# untitled.net
KiCad netlist of a schematic drawn in EAGLE
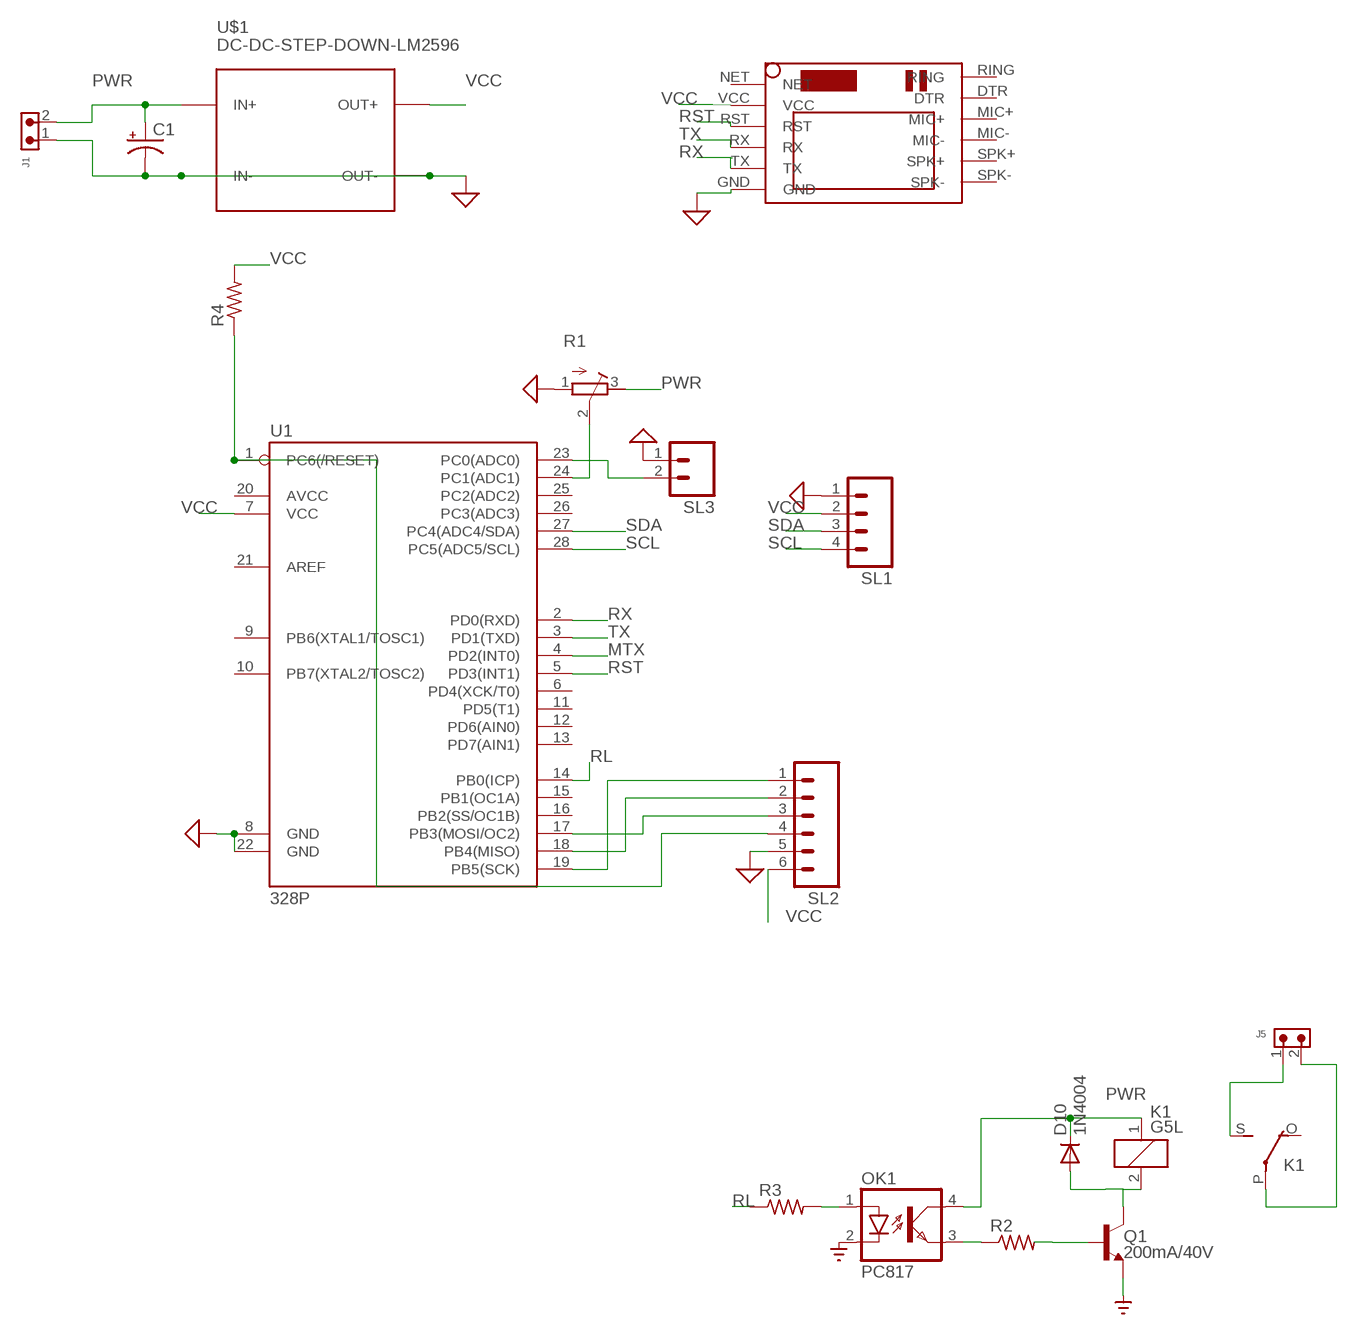
[diagram p0: schematic, sheet 1]

(export (version "E")
  (design (tool "Eeschema 10.0.6"))
  (components
    (comp (ref "C1")
      (value "CPOL-USE7.5-16")
      (footprint "eagle-import:E7,5-16")
      (libsource (lib "eagle-import") (part "CPOL-USE7.5-16"))
    )
    (comp (ref "D10")
      (value "1N4004")
      (footprint "eagle-import:DO41-10")
      (libsource (lib "eagle-import") (part "1N4004"))
    )
    (comp (ref "J1")
      (value "691305530002")
      (footprint "eagle-import:691305530002")
      (libsource (lib "eagle-import") (part "691305530002"))
    )
    (comp (ref "J5")
      (value "691305530002")
      (footprint "eagle-import:691305530002")
      (libsource (lib "eagle-import") (part "691305530002"))
    )
    (comp (ref "K1")
      (value "G5L")
      (footprint "eagle-import:G5LE")
      (libsource (lib "eagle-import") (part "G5L"))
    )
    (comp (ref "OK1")
      (value "PC817")
      (footprint "eagle-import:DIL04")
      (fields (field (name "MPN") "PC817X4J000F"))
      (libsource (lib "eagle-import") (part "PC817"))
    )
    (comp (ref "Q1")
      (value "200mA/40V")
      (footprint "eagle-import:TO-92")
      (libsource (lib "eagle-import") (part "TRANS_NPN-2N3904"))
    )
    (comp (ref "R1")
      (value "R-TRIMM3296Y")
      (footprint "eagle-import:RTRIM3296Y")
      (libsource (lib "eagle-import") (part "R-TRIMM3296Y"))
    )
    (comp (ref "R2")
      (value "R-US_0207/10")
      (footprint "eagle-import:0207_10")
      (libsource (lib "eagle-import") (part "R-US_0207/10"))
    )
    (comp (ref "R3")
      (value "R-US_0207/12")
      (footprint "eagle-import:0207_12")
      (libsource (lib "eagle-import") (part "adafruit_420_R-US_0207/12"))
    )
    (comp (ref "R4")
      (value "R-US_0207/10")
      (footprint "eagle-import:0207_10")
      (libsource (lib "eagle-import") (part "R-US_0207/10"))
    )
    (comp (ref "SL1")
      (value "M04")
      (footprint "eagle-import:04P")
      (libsource (lib "eagle-import") (part "M04"))
    )
    (comp (ref "SL2")
      (value "M06")
      (footprint "eagle-import:06P")
      (libsource (lib "eagle-import") (part "M06"))
    )
    (comp (ref "SL3")
      (value "M02")
      (footprint "eagle-import:02P")
      (libsource (lib "eagle-import") (part "M02"))
    )
    (comp (ref "U$1")
      (value "DC-DC-STEP-DOWN-LM2596")
      (footprint "eagle-import:DC-DC-STEP-DOWN-LM2596")
      (libsource (lib "eagle-import") (part "DC-DC-STEP-DOWN-LM2596"))
    )
    (comp (ref "U$2")
      (value "SIM800LMODULE")
      (footprint "eagle-import:SIM800LMODULE")
      (libsource (lib "eagle-import") (part "SIM800LMODULE"))
    )
    (comp (ref "U1")
      (value "328P")
      (footprint "eagle-import:DIP28")
      (libsource (lib "eagle-import") (part "ATMEGA328P_PDIP"))
    )
  )
  (nets
    (net (code "1") (name "/MTX") (class "Default")
      (node (ref "U1") (pin "4") (pinfunction "PD2(INT0)_4") (pintype "bidirectional"))
    )
    (net (code "2") (name "/PWR") (class "Default")
      (node (ref "C1") (pin "+") (pinfunction "+_+") (pintype "passive"))
      (node (ref "D10") (pin "C") (pinfunction "C_C") (pintype "passive"))
      (node (ref "J1") (pin "2") (pinfunction "2_2") (pintype "passive"))
      (node (ref "K1") (pin "1") (pinfunction "1_1") (pintype "passive"))
      (node (ref "OK1") (pin "4") (pinfunction "COL_4") (pintype "passive"))
      (node (ref "R1") (pin "3") (pinfunction "E_3") (pintype "passive"))
      (node (ref "U$1") (pin "IN+") (pinfunction "IN+_IN+") (pintype "bidirectional"))
    )
    (net (code "3") (name "/RL") (class "Default")
      (node (ref "R3") (pin "1") (pinfunction "1_1") (pintype "passive"))
      (node (ref "U1") (pin "14") (pinfunction "PB0(ICP)_14") (pintype "bidirectional"))
    )
    (net (code "4") (name "/RST") (class "Default")
      (node (ref "U$2") (pin "RST") (pinfunction "RST_RST") (pintype "bidirectional"))
      (node (ref "U1") (pin "5") (pinfunction "PD3(INT1)_5") (pintype "bidirectional"))
    )
    (net (code "5") (name "/RX") (class "Default")
      (node (ref "U$2") (pin "TX") (pinfunction "TX_TX") (pintype "bidirectional"))
      (node (ref "U1") (pin "2") (pinfunction "PD0(RXD)_2") (pintype "bidirectional"))
    )
    (net (code "6") (name "/SCL") (class "Default")
      (node (ref "SL1") (pin "4") (pinfunction "4_4") (pintype "passive"))
      (node (ref "U1") (pin "28") (pinfunction "PC5(ADC5/SCL)_28") (pintype "bidirectional"))
    )
    (net (code "7") (name "/SDA") (class "Default")
      (node (ref "SL1") (pin "3") (pinfunction "3_3") (pintype "passive"))
      (node (ref "U1") (pin "27") (pinfunction "PC4(ADC4/SDA)_27") (pintype "bidirectional"))
    )
    (net (code "8") (name "/TX") (class "Default")
      (node (ref "U$2") (pin "RX") (pinfunction "RX_RX") (pintype "bidirectional"))
      (node (ref "U1") (pin "3") (pinfunction "PD1(TXD)_3") (pintype "bidirectional"))
    )
    (net (code "9") (name "/VCC") (class "Default")
      (node (ref "R4") (pin "2") (pinfunction "2_2") (pintype "passive"))
      (node (ref "SL1") (pin "2") (pinfunction "2_2") (pintype "passive"))
      (node (ref "SL2") (pin "6") (pinfunction "6_6") (pintype "passive"))
      (node (ref "U$1") (pin "OUT+") (pinfunction "OUT+_OUT+") (pintype "bidirectional"))
      (node (ref "U$2") (pin "VCC") (pinfunction "VCC_VCC") (pintype "bidirectional"))
      (node (ref "U1") (pin "7") (pinfunction "VCC_7") (pintype "bidirectional"))
    )
    (net (code "10") (name "Net-(J5-Pad1)") (class "Default")
      (node (ref "J5") (pin "1") (pinfunction "1_1") (pintype "passive"))
      (node (ref "K1") (pin "S") (pinfunction "S_S") (pintype "passive"))
    )
    (net (code "11") (name "Net-(J5-Pad2)") (class "Default")
      (node (ref "J5") (pin "2") (pinfunction "2_2") (pintype "passive"))
      (node (ref "K1") (pin "P") (pinfunction "P_P") (pintype "passive"))
    )
    (net (code "12") (name "Net-(OK1-A)") (class "Default")
      (node (ref "OK1") (pin "1") (pinfunction "A_1") (pintype "passive"))
      (node (ref "R3") (pin "2") (pinfunction "2_2") (pintype "passive"))
    )
    (net (code "13") (name "Net-(OK1-EMIT)") (class "Default")
      (node (ref "OK1") (pin "3") (pinfunction "EMIT_3") (pintype "passive"))
      (node (ref "R2") (pin "1") (pinfunction "1_1") (pintype "passive"))
    )
    (net (code "14") (name "Net-(Q1-B)") (class "Default")
      (node (ref "Q1") (pin "2") (pinfunction "B_2") (pintype "passive"))
      (node (ref "R2") (pin "2") (pinfunction "2_2") (pintype "passive"))
    )
    (net (code "15") (name "Net-(Q1-C)") (class "Default")
      (node (ref "D10") (pin "A") (pinfunction "A_A") (pintype "passive"))
      (node (ref "K1") (pin "2") (pinfunction "2_2") (pintype "passive"))
      (node (ref "Q1") (pin "3") (pinfunction "C_3") (pintype "passive"))
    )
    (net (code "16") (name "Net-(R1-S)") (class "Default")
      (node (ref "R1") (pin "2") (pinfunction "S_2") (pintype "passive"))
      (node (ref "U1") (pin "24") (pinfunction "PC1(ADC1)_24") (pintype "bidirectional"))
    )
    (net (code "17") (name "Net-(U1-PB3(MOSI{slash}OC2))") (class "Default")
      (node (ref "SL2") (pin "3") (pinfunction "3_3") (pintype "passive"))
      (node (ref "U1") (pin "17") (pinfunction "PB3(MOSI/OC2)_17") (pintype "bidirectional"))
    )
    (net (code "18") (name "Net-(U1-PB4(MISO))") (class "Default")
      (node (ref "SL2") (pin "2") (pinfunction "2_2") (pintype "passive"))
      (node (ref "U1") (pin "18") (pinfunction "PB4(MISO)_18") (pintype "bidirectional"))
    )
    (net (code "19") (name "Net-(U1-PB5(SCK))") (class "Default")
      (node (ref "SL2") (pin "1") (pinfunction "1_1") (pintype "passive"))
      (node (ref "U1") (pin "19") (pinfunction "PB5(SCK)_19") (pintype "bidirectional"))
    )
    (net (code "20") (name "Net-(U1-PC0(ADC0))") (class "Default")
      (node (ref "SL3") (pin "2") (pinfunction "2_2") (pintype "passive"))
      (node (ref "U1") (pin "23") (pinfunction "PC0(ADC0)_23") (pintype "bidirectional"))
    )
    (net (code "21") (name "Net-(U1-PC6({slash}RESET))") (class "Default")
      (node (ref "R4") (pin "1") (pinfunction "1_1") (pintype "passive"))
      (node (ref "SL2") (pin "4") (pinfunction "4_4") (pintype "passive"))
      (node (ref "U1") (pin "1") (pinfunction "PC6(/RESET)_1") (pintype "bidirectional"))
    )
    (net (code "22") (name "SUP") (class "Default")
      (node (ref "C1") (pin "-") (pinfunction "-_-") (pintype "passive"))
      (node (ref "J1") (pin "1") (pinfunction "1_1") (pintype "passive"))
      (node (ref "OK1") (pin "2") (pinfunction "C_2") (pintype "passive"))
      (node (ref "Q1") (pin "1") (pinfunction "E_1") (pintype "passive"))
      (node (ref "R1") (pin "1") (pinfunction "A_1") (pintype "passive"))
      (node (ref "SL1") (pin "1") (pinfunction "1_1") (pintype "passive"))
      (node (ref "SL2") (pin "5") (pinfunction "5_5") (pintype "passive"))
      (node (ref "SL3") (pin "1") (pinfunction "1_1") (pintype "passive"))
      (node (ref "U$1") (pin "IN-") (pinfunction "IN-_IN-") (pintype "bidirectional"))
      (node (ref "U$1") (pin "OUT-") (pinfunction "OUT-_OUT-") (pintype "bidirectional"))
      (node (ref "U$2") (pin "GND") (pinfunction "GND_GND") (pintype "bidirectional"))
      (node (ref "U1") (pin "22") (pinfunction "GND_22") (pintype "bidirectional"))
      (node (ref "U1") (pin "8") (pinfunction "GND_8") (pintype "bidirectional"))
    )
    (net (code "23") (name "unconnected-(K1-PadO)") (class "Default")
      (node (ref "K1") (pin "O") (pinfunction "O_O") (pintype "passive"))
    )
    (net (code "24") (name "unconnected-(U$2-PadDTR)") (class "Default")
      (node (ref "U$2") (pin "DTR") (pinfunction "DTR_DTR") (pintype "bidirectional"))
    )
    (net (code "25") (name "unconnected-(U$2-PadMIC+)") (class "Default")
      (node (ref "U$2") (pin "MIC+") (pinfunction "MIC+_MIC+") (pintype "bidirectional"))
    )
    (net (code "26") (name "unconnected-(U$2-PadMIC-)") (class "Default")
      (node (ref "U$2") (pin "MIC-") (pinfunction "MIC-_MIC-") (pintype "bidirectional"))
    )
    (net (code "27") (name "unconnected-(U$2-PadNET)") (class "Default")
      (node (ref "U$2") (pin "NET") (pinfunction "NET_NET") (pintype "bidirectional"))
    )
    (net (code "28") (name "unconnected-(U$2-PadRING)") (class "Default")
      (node (ref "U$2") (pin "RING") (pinfunction "RING_RING") (pintype "bidirectional"))
    )
    (net (code "29") (name "unconnected-(U$2-PadSPK+)") (class "Default")
      (node (ref "U$2") (pin "SPK+") (pinfunction "SPK+_SPK+") (pintype "bidirectional"))
    )
    (net (code "30") (name "unconnected-(U$2-PadSPK-)") (class "Default")
      (node (ref "U$2") (pin "SPK-") (pinfunction "SPK-_SPK-") (pintype "bidirectional"))
    )
    (net (code "31") (name "unconnected-(U1-AREF-Pad21)") (class "Default")
      (node (ref "U1") (pin "21") (pinfunction "AREF_21") (pintype "bidirectional"))
    )
    (net (code "32") (name "unconnected-(U1-AVCC-Pad20)") (class "Default")
      (node (ref "U1") (pin "20") (pinfunction "AVCC_20") (pintype "bidirectional"))
    )
    (net (code "33") (name "unconnected-(U1-PB1(OC1A)-Pad15)") (class "Default")
      (node (ref "U1") (pin "15") (pinfunction "PB1(OC1A)_15") (pintype "bidirectional"))
    )
    (net (code "34") (name "unconnected-(U1-PB2(SS{slash}OC1B)-Pad16)") (class "Default")
      (node (ref "U1") (pin "16") (pinfunction "PB2(SS/OC1B)_16") (pintype "bidirectional"))
    )
    (net (code "35") (name "unconnected-(U1-PB6(XTAL1{slash}TOSC1)-Pad9)") (class "Default")
      (node (ref "U1") (pin "9") (pinfunction "PB6(XTAL1/TOSC1)_9") (pintype "bidirectional"))
    )
    (net (code "36") (name "unconnected-(U1-PB7(XTAL2{slash}TOSC2)-Pad10)") (class "Default")
      (node (ref "U1") (pin "10") (pinfunction "PB7(XTAL2/TOSC2)_10") (pintype "bidirectional"))
    )
    (net (code "37") (name "unconnected-(U1-PC2(ADC2)-Pad25)") (class "Default")
      (node (ref "U1") (pin "25") (pinfunction "PC2(ADC2)_25") (pintype "bidirectional"))
    )
    (net (code "38") (name "unconnected-(U1-PC3(ADC3)-Pad26)") (class "Default")
      (node (ref "U1") (pin "26") (pinfunction "PC3(ADC3)_26") (pintype "bidirectional"))
    )
    (net (code "39") (name "unconnected-(U1-PD4(XCK{slash}T0)-Pad6)") (class "Default")
      (node (ref "U1") (pin "6") (pinfunction "PD4(XCK/T0)_6") (pintype "bidirectional"))
    )
    (net (code "40") (name "unconnected-(U1-PD5(T1)-Pad11)") (class "Default")
      (node (ref "U1") (pin "11") (pinfunction "PD5(T1)_11") (pintype "bidirectional"))
    )
    (net (code "41") (name "unconnected-(U1-PD6(AIN0)-Pad12)") (class "Default")
      (node (ref "U1") (pin "12") (pinfunction "PD6(AIN0)_12") (pintype "bidirectional"))
    )
    (net (code "42") (name "unconnected-(U1-PD7(AIN1)-Pad13)") (class "Default")
      (node (ref "U1") (pin "13") (pinfunction "PD7(AIN1)_13") (pintype "bidirectional"))
    )
  )
)
